# DSO_CPLD.net
KiCad netlist of a schematic drawn in Altium Designer
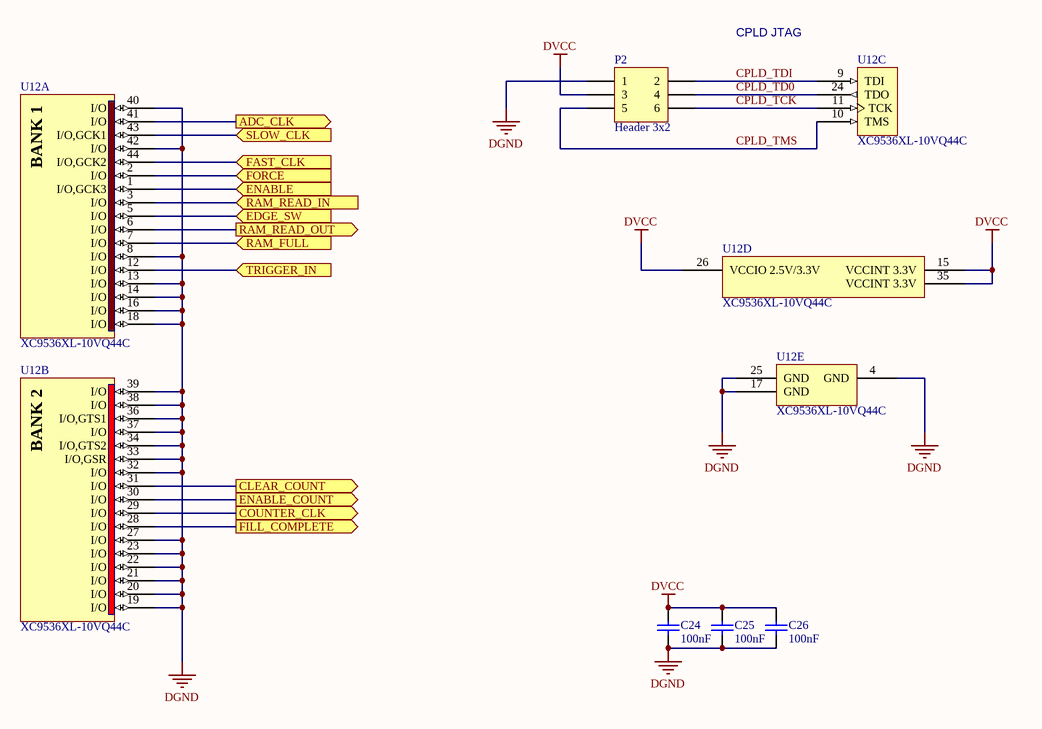
[diagram p0: DSO_CPLD.SchDoc]

(export (version "E")
  (design (tool "Eeschema 10.0.6"))
  (components
    (comp (ref "C24")
      (value "100nF")
      (footprint "0805C")
      (description "Capacitor")
      (fields (field (name "REVIEWED BY") "RM - 2018/08/05"))
      (libsource (lib "DSO") (part "C"))
    )
    (comp (ref "C25")
      (value "100nF")
      (footprint "0805C")
      (description "Capacitor")
      (fields (field (name "REVIEWED BY") "RM - 2018/08/05"))
      (libsource (lib "DSO") (part "C"))
    )
    (comp (ref "C26")
      (value "100nF")
      (footprint "0805C")
      (description "Capacitor")
      (fields (field (name "REVIEWED BY") "RM - 2018/08/05"))
      (libsource (lib "DSO") (part "C"))
    )
    (comp (ref "P2")
      (value "Header 3x2")
      (footprint "HDR3x2")
      (description "Header, 5-Pin")
      (fields (field (name "REVIEWED BY") "RM - 2018/08/05"))
      (libsource (lib "DSO") (part "Header 3x2"))
    )
    (comp (ref "U12")
      (value "XC9536XL-10VQ44C")
      (footprint "VQ44_L")
      (fields (field (name "REVIEWED BY") "RM - 2018/08/05"))
      (libsource (lib "DSO") (part "XC9536XL-10VQG44C"))
    )
  )
  (nets
    (net (code "1") (name "/ADC_CLK") (class "Default")
      (node (ref "U12") (pin "41") (pinfunction "I/O_41") (pintype "bidirectional"))
    )
    (net (code "2") (name "/CLEAR_COUNT") (class "Default")
      (node (ref "U12") (pin "31") (pinfunction "I/O_31") (pintype "bidirectional"))
    )
    (net (code "3") (name "/COUNTER_CLK") (class "Default")
      (node (ref "U12") (pin "29") (pinfunction "I/O_29") (pintype "bidirectional"))
    )
    (net (code "4") (name "/CPLD_TCK") (class "Default")
      (node (ref "P2") (pin "6") (pinfunction "6_6") (pintype "passive"))
      (node (ref "U12") (pin "11") (pinfunction "TCK_11") (pintype "input"))
    )
    (net (code "5") (name "/CPLD_TD0") (class "Default")
      (node (ref "P2") (pin "4") (pinfunction "4_4") (pintype "passive"))
      (node (ref "U12") (pin "24") (pinfunction "TDO_24") (pintype "output"))
    )
    (net (code "6") (name "/CPLD_TDI") (class "Default")
      (node (ref "P2") (pin "2") (pinfunction "2_2") (pintype "passive"))
      (node (ref "U12") (pin "9") (pinfunction "TDI_9") (pintype "input"))
    )
    (net (code "7") (name "/CPLD_TMS") (class "Default")
      (node (ref "P2") (pin "5") (pinfunction "5_5") (pintype "passive"))
      (node (ref "U12") (pin "10") (pinfunction "TMS_10") (pintype "input"))
    )
    (net (code "8") (name "/EDGE_SW") (class "Default")
      (node (ref "U12") (pin "5") (pinfunction "I/O_5") (pintype "bidirectional"))
    )
    (net (code "9") (name "/ENABLE") (class "Default")
      (node (ref "U12") (pin "1") (pinfunction "I/O,GCK3_1") (pintype "bidirectional"))
    )
    (net (code "10") (name "/ENABLE_COUNT") (class "Default")
      (node (ref "U12") (pin "30") (pinfunction "I/O_30") (pintype "bidirectional"))
    )
    (net (code "11") (name "/FAST_CLK") (class "Default")
      (node (ref "U12") (pin "44") (pinfunction "I/O,GCK2_44") (pintype "bidirectional"))
    )
    (net (code "12") (name "/FILL_COMPLETE") (class "Default")
      (node (ref "U12") (pin "28") (pinfunction "I/O_28") (pintype "bidirectional"))
    )
    (net (code "13") (name "/FORCE") (class "Default")
      (node (ref "U12") (pin "2") (pinfunction "I/O_2") (pintype "bidirectional"))
    )
    (net (code "14") (name "/RAM_FULL") (class "Default")
      (node (ref "U12") (pin "7") (pinfunction "I/O_7") (pintype "bidirectional"))
    )
    (net (code "15") (name "/RAM_READ_IN") (class "Default")
      (node (ref "U12") (pin "3") (pinfunction "I/O_3") (pintype "bidirectional"))
    )
    (net (code "16") (name "/RAM_READ_OUT") (class "Default")
      (node (ref "U12") (pin "6") (pinfunction "I/O_6") (pintype "bidirectional"))
    )
    (net (code "17") (name "/SLOW_CLK") (class "Default")
      (node (ref "U12") (pin "43") (pinfunction "I/O,GCK1_43") (pintype "bidirectional"))
    )
    (net (code "18") (name "/TRIGGER_IN") (class "Default")
      (node (ref "U12") (pin "12") (pinfunction "I/O_12") (pintype "bidirectional"))
    )
    (net (code "19") (name "DGND") (class "Default")
      (node (ref "C24") (pin "2") (pinfunction "2_2") (pintype "passive"))
      (node (ref "C25") (pin "2") (pinfunction "2_2") (pintype "passive"))
      (node (ref "C26") (pin "2") (pinfunction "2_2") (pintype "passive"))
      (node (ref "P2") (pin "1") (pinfunction "1_1") (pintype "passive"))
      (node (ref "U12") (pin "13") (pinfunction "I/O_13") (pintype "bidirectional"))
      (node (ref "U12") (pin "14") (pinfunction "I/O_14") (pintype "bidirectional"))
      (node (ref "U12") (pin "16") (pinfunction "I/O_16") (pintype "bidirectional"))
      (node (ref "U12") (pin "17") (pinfunction "GND_17") (pintype "power_in"))
      (node (ref "U12") (pin "18") (pinfunction "I/O_18") (pintype "bidirectional"))
      (node (ref "U12") (pin "19") (pinfunction "I/O_19") (pintype "bidirectional"))
      (node (ref "U12") (pin "20") (pinfunction "I/O_20") (pintype "bidirectional"))
      (node (ref "U12") (pin "21") (pinfunction "I/O_21") (pintype "bidirectional"))
      (node (ref "U12") (pin "22") (pinfunction "I/O_22") (pintype "bidirectional"))
      (node (ref "U12") (pin "23") (pinfunction "I/O_23") (pintype "bidirectional"))
      (node (ref "U12") (pin "25") (pinfunction "GND_25") (pintype "power_in"))
      (node (ref "U12") (pin "27") (pinfunction "I/O_27") (pintype "bidirectional"))
      (node (ref "U12") (pin "32") (pinfunction "I/O_32") (pintype "bidirectional"))
      (node (ref "U12") (pin "33") (pinfunction "I/O,GSR_33") (pintype "bidirectional"))
      (node (ref "U12") (pin "34") (pinfunction "I/O,GTS2_34") (pintype "bidirectional"))
      (node (ref "U12") (pin "36") (pinfunction "I/O,GTS1_36") (pintype "bidirectional"))
      (node (ref "U12") (pin "37") (pinfunction "I/O_37") (pintype "bidirectional"))
      (node (ref "U12") (pin "38") (pinfunction "I/O_38") (pintype "bidirectional"))
      (node (ref "U12") (pin "39") (pinfunction "I/O_39") (pintype "bidirectional"))
      (node (ref "U12") (pin "4") (pinfunction "GND_4") (pintype "power_in"))
      (node (ref "U12") (pin "40") (pinfunction "I/O_40") (pintype "bidirectional"))
      (node (ref "U12") (pin "42") (pinfunction "I/O_42") (pintype "bidirectional"))
      (node (ref "U12") (pin "8") (pinfunction "I/O_8") (pintype "bidirectional"))
    )
    (net (code "20") (name "DVCC") (class "Default")
      (node (ref "C24") (pin "1") (pinfunction "1_1") (pintype "passive"))
      (node (ref "C25") (pin "1") (pinfunction "1_1") (pintype "passive"))
      (node (ref "C26") (pin "1") (pinfunction "1_1") (pintype "passive"))
      (node (ref "P2") (pin "3") (pinfunction "3_3") (pintype "passive"))
      (node (ref "U12") (pin "15") (pinfunction "VCCINT_3.3V_15") (pintype "power_in"))
      (node (ref "U12") (pin "26") (pinfunction "VCCIO_2.5V/3.3V_26") (pintype "power_in"))
      (node (ref "U12") (pin "35") (pinfunction "VCCINT_3.3V_35") (pintype "power_in"))
    )
  )
)
